# Schematics.net
KiCad netlist of a schematic drawn in Altium Designer
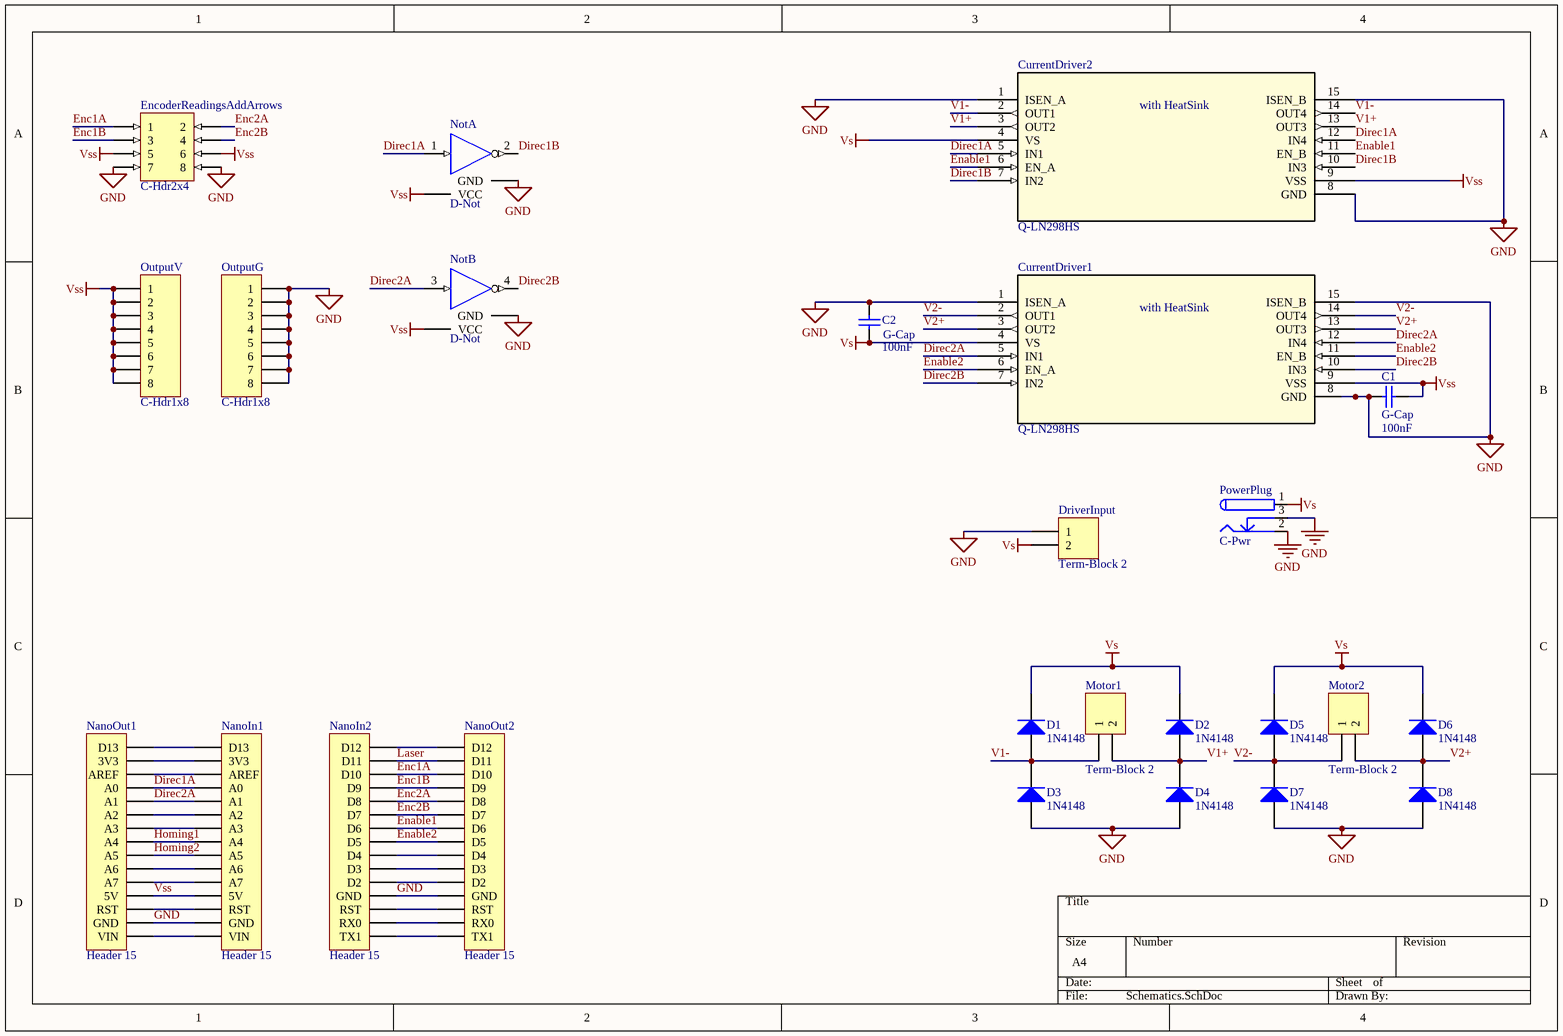
[diagram p0: Schematics.SchDoc]

(export (version "E")
  (design (tool "Eeschema 10.0.6"))
  (components
    (comp (ref "C1")
      (value "G-Cap")
      (footprint "Cap2.54mm_LGE1.0")
      (description "Capacitor (specify value)")
      (fields (field (name "ALTIUM_VALUE") "100nF") (field (name "PUBLISHER") "Altium Limited"))
      (libsource (lib "PartsDatabaseV16.1") (part "G-Cap"))
    )
    (comp (ref "C2")
      (value "G-Cap")
      (footprint "Cap2.54mm_LGE1.0")
      (description "Capacitor (specify value)")
      (fields (field (name "ALTIUM_VALUE") "100nF") (field (name "PUBLISHER") "Altium Limited"))
      (libsource (lib "PartsDatabaseV16.1") (part "G-Cap"))
    )
    (comp (ref "CurrentDriver1")
      (value "Q-LN298HS")
      (footprint "Multiwatt15_V_ELEC391HS")
      (description "LN298 - IC Bridge Driver Par 15Multiwatt")
      (fields
        (field (name "MANUFACTURER_PART_NUMBER") "L298N")
        (field (name "COPYRIGHT") "Copyright (C) 2015 Accelerated Designs. All rights reserved")
      )
      (libsource (lib "Additional Parts 391") (part "Q-LN298HS"))
    )
    (comp (ref "CurrentDriver2")
      (value "Q-LN298HS")
      (footprint "Multiwatt15_V_ELEC391HS")
      (description "LN298 - IC Bridge Driver Par 15Multiwatt")
      (fields
        (field (name "MANUFACTURER_PART_NUMBER") "L298N")
        (field (name "COPYRIGHT") "Copyright (C) 2015 Accelerated Designs. All rights reserved")
      )
      (libsource (lib "Additional Parts 391") (part "Q-LN298HS"))
    )
    (comp (ref "D1")
      (value "1N4148")
      (footprint "DO-41_XLGE1.2")
      (description "High-speed Diode")
      (libsource (lib "PartsDatabaseV16.1") (part "T-DiodeRect"))
    )
    (comp (ref "D2")
      (value "1N4148")
      (footprint "DO-41_XLGE1.2")
      (description "High-speed Diode")
      (libsource (lib "PartsDatabaseV16.1") (part "T-DiodeRect"))
    )
    (comp (ref "D3")
      (value "1N4148")
      (footprint "DO-41_XLGE1.2")
      (description "High-speed Diode")
      (libsource (lib "PartsDatabaseV16.1") (part "T-DiodeRect"))
    )
    (comp (ref "D4")
      (value "1N4148")
      (footprint "DO-41_XLGE1.2")
      (description "High-speed Diode")
      (libsource (lib "PartsDatabaseV16.1") (part "T-DiodeRect"))
    )
    (comp (ref "D5")
      (value "1N4148")
      (footprint "DO-41_XLGE1.2")
      (description "High-speed Diode")
      (libsource (lib "PartsDatabaseV16.1") (part "T-DiodeRect"))
    )
    (comp (ref "D6")
      (value "1N4148")
      (footprint "DO-41_XLGE1.2")
      (description "High-speed Diode")
      (libsource (lib "PartsDatabaseV16.1") (part "T-DiodeRect"))
    )
    (comp (ref "D7")
      (value "1N4148")
      (footprint "DO-41_XLGE1.2")
      (description "High-speed Diode")
      (libsource (lib "PartsDatabaseV16.1") (part "T-DiodeRect"))
    )
    (comp (ref "D8")
      (value "1N4148")
      (footprint "DO-41_XLGE1.2")
      (description "High-speed Diode")
      (libsource (lib "PartsDatabaseV16.1") (part "T-DiodeRect"))
    )
    (comp (ref "DriverInput")
      (value "Term-Block 2")
      (footprint "TERM-BLOCK-5.08MM-2POS")
      (description "Terminal-Block 1x2")
      (fields (field (name "PUBLISHER") "Altium Limited"))
      (libsource (lib "") (part "C-Block2_1"))
    )
    (comp (ref "EncoderReadingsAddArrows")
      (value "C-Hdr2x4")
      (footprint "HDR2X4_LGE1.0")
      (description "Header, 4-Pin, Dual row")
      (fields (field (name "PUBLISHER") "Altium Limited"))
      (libsource (lib "PartsDatabaseV16.1") (part "C-Hdr2x4"))
    )
    (comp (ref "Motor1")
      (value "Term-Block 2")
      (footprint "TERM-BLOCK-5.08MM-2POS")
      (description "Terminal-Block 1x2")
      (fields (field (name "PUBLISHER") "Altium Limited"))
      (libsource (lib "PartsDatabaseV16.1") (part "C-Block2"))
    )
    (comp (ref "Motor2")
      (value "Term-Block 2")
      (footprint "TERM-BLOCK-5.08MM-2POS")
      (description "Terminal-Block 1x2")
      (fields (field (name "PUBLISHER") "Altium Limited"))
      (libsource (lib "PartsDatabaseV16.1") (part "C-Block2"))
    )
    (comp (ref "NanoIn1")
      (value "Header 15")
      (footprint "HDR1X15")
      (description "Header, 15-Pin")
      (fields (field (name "PUBLISHER") "Altium Limited"))
      (libsource (lib "") (part "Header 15_1"))
    )
    (comp (ref "NanoIn2")
      (value "Header 15")
      (footprint "HDR1X15")
      (description "Header, 15-Pin")
      (fields (field (name "PUBLISHER") "Altium Limited"))
      (libsource (lib "Miscellaneous Connectors") (part "Header 15"))
    )
    (comp (ref "NanoOut1")
      (value "Header 15")
      (footprint "HDR1X15")
      (description "Header, 15-Pin")
      (fields (field (name "PUBLISHER") "Altium Limited"))
      (libsource (lib "Miscellaneous Connectors") (part "Header 15"))
    )
    (comp (ref "NanoOut2")
      (value "Header 15")
      (footprint "HDR1X15")
      (description "Header, 15-Pin")
      (fields (field (name "PUBLISHER") "Altium Limited"))
      (libsource (lib "") (part "Header 15_2"))
    )
    (comp (ref "Not")
      (value "D-Not")
      (footprint "DIP14_LGE1.0")
      (description "Hex NOT gate (inverter)")
      (fields (field (name "PUBLISHER") "Altium Limited"))
      (libsource (lib "PartsDatabaseV16.1") (part "D-Not"))
    )
    (comp (ref "OutputG")
      (value "C-Hdr1x8")
      (footprint "HDR1X8_LGE1.0")
      (description "Header, 8-Pin")
      (fields (field (name "PUBLISHER") "Altium Limited"))
      (libsource (lib "") (part "C-Hdr1x8_1"))
    )
    (comp (ref "OutputV")
      (value "C-Hdr1x8")
      (footprint "HDR1X8_LGE1.0")
      (description "Header, 8-Pin")
      (fields (field (name "PUBLISHER") "Altium Limited"))
      (libsource (lib "PartsDatabaseV16.1") (part "C-Hdr1x8"))
    )
    (comp (ref "PowerPlug")
      (value "C-Pwr")
      (footprint "KLD_XLGE1.2")
      (description "Low Voltage Power Supply Connector")
      (fields (field (name "PUBLISHER") "Altium Limited"))
      (libsource (lib "PartsDatabaseV16.1") (part "C-Pwr"))
    )
  )
  (nets
    (net (code "1") (name "/Direc1A") (class "Default")
      (node (ref "CurrentDriver2") (pin "12") (pinfunction "IN4_12") (pintype "input"))
      (node (ref "CurrentDriver2") (pin "5") (pinfunction "IN1_5") (pintype "input"))
      (node (ref "NanoIn1") (pin "4") (pinfunction "A0_4") (pintype "passive"))
      (node (ref "NanoOut1") (pin "4") (pinfunction "A0_4") (pintype "passive"))
      (node (ref "Not") (pin "1") (pinfunction "A_1") (pintype "input"))
    )
    (net (code "2") (name "/Direc1B") (class "Default")
      (node (ref "CurrentDriver2") (pin "10") (pinfunction "IN3_10") (pintype "input"))
      (node (ref "CurrentDriver2") (pin "7") (pinfunction "IN2_7") (pintype "input"))
      (node (ref "Not") (pin "2") (pinfunction "Y_2") (pintype "output"))
    )
    (net (code "3") (name "/Direc2A") (class "Default")
      (node (ref "CurrentDriver1") (pin "12") (pinfunction "IN4_12") (pintype "input"))
      (node (ref "CurrentDriver1") (pin "5") (pinfunction "IN1_5") (pintype "input"))
      (node (ref "NanoIn1") (pin "5") (pinfunction "A1_5") (pintype "passive"))
      (node (ref "NanoOut1") (pin "5") (pinfunction "A1_5") (pintype "passive"))
      (node (ref "Not") (pin "3") (pinfunction "A_3") (pintype "input"))
    )
    (net (code "4") (name "/Direc2B") (class "Default")
      (node (ref "CurrentDriver1") (pin "10") (pinfunction "IN3_10") (pintype "input"))
      (node (ref "CurrentDriver1") (pin "7") (pinfunction "IN2_7") (pintype "input"))
      (node (ref "Not") (pin "4") (pinfunction "Y_4") (pintype "output"))
    )
    (net (code "5") (name "/Enable1") (class "Default")
      (node (ref "CurrentDriver2") (pin "11") (pinfunction "EN_B_11") (pintype "input"))
      (node (ref "CurrentDriver2") (pin "6") (pinfunction "EN_A_6") (pintype "input"))
      (node (ref "NanoIn2") (pin "7") (pinfunction "A3_7") (pintype "passive"))
      (node (ref "NanoOut2") (pin "7") (pinfunction "D6_7") (pintype "passive"))
    )
    (net (code "6") (name "/Enable2") (class "Default")
      (node (ref "CurrentDriver1") (pin "11") (pinfunction "EN_B_11") (pintype "input"))
      (node (ref "CurrentDriver1") (pin "6") (pinfunction "EN_A_6") (pintype "input"))
      (node (ref "NanoIn2") (pin "8") (pinfunction "A4_8") (pintype "passive"))
      (node (ref "NanoOut2") (pin "8") (pinfunction "D5_8") (pintype "passive"))
    )
    (net (code "7") (name "/Enc1A") (class "Default")
      (node (ref "EncoderReadingsAddArrows") (pin "1") (pinfunction "1_1") (pintype "input"))
      (node (ref "NanoIn2") (pin "3") (pinfunction "AREF_3") (pintype "passive"))
      (node (ref "NanoOut2") (pin "3") (pinfunction "D10_3") (pintype "passive"))
    )
    (net (code "8") (name "/Enc1B") (class "Default")
      (node (ref "EncoderReadingsAddArrows") (pin "3") (pinfunction "3_3") (pintype "input"))
      (node (ref "NanoIn2") (pin "4") (pinfunction "A0_4") (pintype "passive"))
      (node (ref "NanoOut2") (pin "4") (pinfunction "D9_4") (pintype "passive"))
    )
    (net (code "9") (name "/Enc2A") (class "Default")
      (node (ref "EncoderReadingsAddArrows") (pin "2") (pinfunction "2_2") (pintype "input"))
      (node (ref "NanoIn2") (pin "5") (pinfunction "A1_5") (pintype "passive"))
      (node (ref "NanoOut2") (pin "5") (pinfunction "D8_5") (pintype "passive"))
    )
    (net (code "10") (name "/Enc2B") (class "Default")
      (node (ref "EncoderReadingsAddArrows") (pin "4") (pinfunction "4_4") (pintype "input"))
      (node (ref "NanoIn2") (pin "6") (pinfunction "A2_6") (pintype "passive"))
      (node (ref "NanoOut2") (pin "6") (pinfunction "D7_6") (pintype "passive"))
    )
    (net (code "11") (name "/Homing1") (class "Default")
      (node (ref "NanoIn1") (pin "8") (pinfunction "A4_8") (pintype "passive"))
      (node (ref "NanoOut1") (pin "8") (pinfunction "A4_8") (pintype "passive"))
    )
    (net (code "12") (name "/Homing2") (class "Default")
      (node (ref "NanoIn1") (pin "9") (pinfunction "A5_9") (pintype "passive"))
      (node (ref "NanoOut1") (pin "9") (pinfunction "A5_9") (pintype "passive"))
    )
    (net (code "13") (name "/Laser") (class "Default")
      (node (ref "NanoIn2") (pin "2") (pinfunction "3V3_2") (pintype "passive"))
      (node (ref "NanoOut2") (pin "2") (pinfunction "D11_2") (pintype "passive"))
    )
    (net (code "14") (name "/V1+") (class "Default")
      (node (ref "CurrentDriver2") (pin "13") (pinfunction "OUT3_13") (pintype "output"))
      (node (ref "CurrentDriver2") (pin "3") (pinfunction "OUT2_3") (pintype "output"))
      (node (ref "D2") (pin "1") (pinfunction "A_1") (pintype "passive"))
      (node (ref "D4") (pin "2") (pinfunction "K_2") (pintype "passive"))
      (node (ref "Motor1") (pin "2") (pinfunction "2_2") (pintype "passive"))
    )
    (net (code "15") (name "/V1-") (class "Default")
      (node (ref "CurrentDriver2") (pin "14") (pinfunction "OUT4_14") (pintype "output"))
      (node (ref "CurrentDriver2") (pin "2") (pinfunction "OUT1_2") (pintype "output"))
      (node (ref "D1") (pin "1") (pinfunction "A_1") (pintype "passive"))
      (node (ref "D3") (pin "2") (pinfunction "K_2") (pintype "passive"))
      (node (ref "Motor1") (pin "1") (pinfunction "1_1") (pintype "passive"))
    )
    (net (code "16") (name "/V2+") (class "Default")
      (node (ref "CurrentDriver1") (pin "13") (pinfunction "OUT3_13") (pintype "output"))
      (node (ref "CurrentDriver1") (pin "3") (pinfunction "OUT2_3") (pintype "output"))
      (node (ref "D6") (pin "1") (pinfunction "A_1") (pintype "passive"))
      (node (ref "D8") (pin "2") (pinfunction "K_2") (pintype "passive"))
      (node (ref "Motor2") (pin "2") (pinfunction "2_2") (pintype "passive"))
    )
    (net (code "17") (name "/V2-") (class "Default")
      (node (ref "CurrentDriver1") (pin "14") (pinfunction "OUT4_14") (pintype "output"))
      (node (ref "CurrentDriver1") (pin "2") (pinfunction "OUT1_2") (pintype "output"))
      (node (ref "D5") (pin "1") (pinfunction "A_1") (pintype "passive"))
      (node (ref "D7") (pin "2") (pinfunction "K_2") (pintype "passive"))
      (node (ref "Motor2") (pin "1") (pinfunction "1_1") (pintype "passive"))
    )
    (net (code "18") (name "GND") (class "Default")
      (node (ref "C1") (pin "1") (pinfunction "1_1") (pintype "passive"))
      (node (ref "C2") (pin "2") (pinfunction "2_2") (pintype "passive"))
      (node (ref "CurrentDriver1") (pin "1") (pinfunction "ISEN_A_1") (pintype "passive"))
      (node (ref "CurrentDriver1") (pin "15") (pinfunction "ISEN_B_15") (pintype "passive"))
      (node (ref "CurrentDriver1") (pin "8") (pinfunction "GND_8") (pintype "power_in"))
      (node (ref "CurrentDriver2") (pin "1") (pinfunction "ISEN_A_1") (pintype "passive"))
      (node (ref "CurrentDriver2") (pin "15") (pinfunction "ISEN_B_15") (pintype "passive"))
      (node (ref "CurrentDriver2") (pin "8") (pinfunction "GND_8") (pintype "power_in"))
      (node (ref "D3") (pin "1") (pinfunction "A_1") (pintype "passive"))
      (node (ref "D4") (pin "1") (pinfunction "A_1") (pintype "passive"))
      (node (ref "D7") (pin "1") (pinfunction "A_1") (pintype "passive"))
      (node (ref "D8") (pin "1") (pinfunction "A_1") (pintype "passive"))
      (node (ref "DriverInput") (pin "1") (pinfunction "1_1") (pintype "passive"))
      (node (ref "EncoderReadingsAddArrows") (pin "7") (pinfunction "7_7") (pintype "input"))
      (node (ref "EncoderReadingsAddArrows") (pin "8") (pinfunction "8_8") (pintype "input"))
      (node (ref "NanoIn1") (pin "14") (pinfunction "GND_14") (pintype "passive"))
      (node (ref "NanoIn2") (pin "12") (pinfunction "5V_12") (pintype "passive"))
      (node (ref "NanoOut1") (pin "14") (pinfunction "GND_14") (pintype "passive"))
      (node (ref "NanoOut2") (pin "12") (pinfunction "GND_12") (pintype "passive"))
      (node (ref "Not") (pin "7") (pinfunction "GND_7") (pintype "power_in"))
      (node (ref "OutputG") (pin "1") (pinfunction "1_1") (pintype "passive"))
      (node (ref "OutputG") (pin "2") (pinfunction "2_2") (pintype "passive"))
      (node (ref "OutputG") (pin "3") (pinfunction "3_3") (pintype "passive"))
      (node (ref "OutputG") (pin "4") (pinfunction "4_4") (pintype "passive"))
      (node (ref "OutputG") (pin "5") (pinfunction "5_5") (pintype "passive"))
      (node (ref "OutputG") (pin "6") (pinfunction "6_6") (pintype "passive"))
      (node (ref "OutputG") (pin "7") (pinfunction "7_7") (pintype "passive"))
      (node (ref "OutputG") (pin "8") (pinfunction "8_8") (pintype "passive"))
      (node (ref "PowerPlug") (pin "2") (pinfunction "2_2") (pintype "power_in"))
      (node (ref "PowerPlug") (pin "3") (pinfunction "3_3") (pintype "power_in"))
    )
    (net (code "19") (name "Net-(NanoIn1-3V3)") (class "Default")
      (node (ref "NanoIn1") (pin "2") (pinfunction "3V3_2") (pintype "passive"))
      (node (ref "NanoOut1") (pin "2") (pinfunction "3V3_2") (pintype "passive"))
    )
    (net (code "20") (name "Net-(NanoIn1-A2)") (class "Default")
      (node (ref "NanoIn1") (pin "6") (pinfunction "A2_6") (pintype "passive"))
      (node (ref "NanoOut1") (pin "6") (pinfunction "A2_6") (pintype "passive"))
    )
    (net (code "21") (name "Net-(NanoIn1-A3)") (class "Default")
      (node (ref "NanoIn1") (pin "7") (pinfunction "A3_7") (pintype "passive"))
      (node (ref "NanoOut1") (pin "7") (pinfunction "A3_7") (pintype "passive"))
    )
    (net (code "22") (name "Net-(NanoIn1-A6)") (class "Default")
      (node (ref "NanoIn1") (pin "10") (pinfunction "A6_10") (pintype "passive"))
      (node (ref "NanoOut1") (pin "10") (pinfunction "A6_10") (pintype "passive"))
    )
    (net (code "23") (name "Net-(NanoIn1-A7)") (class "Default")
      (node (ref "NanoIn1") (pin "11") (pinfunction "A7_11") (pintype "passive"))
      (node (ref "NanoOut1") (pin "11") (pinfunction "A7_11") (pintype "passive"))
    )
    (net (code "24") (name "Net-(NanoIn1-AREF)") (class "Default")
      (node (ref "NanoIn1") (pin "3") (pinfunction "AREF_3") (pintype "passive"))
      (node (ref "NanoOut1") (pin "3") (pinfunction "AREF_3") (pintype "passive"))
    )
    (net (code "25") (name "Net-(NanoIn1-D13)") (class "Default")
      (node (ref "NanoIn1") (pin "1") (pinfunction "D13_1") (pintype "passive"))
      (node (ref "NanoOut1") (pin "1") (pinfunction "D13_1") (pintype "passive"))
    )
    (net (code "26") (name "Net-(NanoIn1-RST)") (class "Default")
      (node (ref "NanoIn1") (pin "13") (pinfunction "RST_13") (pintype "passive"))
      (node (ref "NanoOut1") (pin "13") (pinfunction "RST_13") (pintype "passive"))
    )
    (net (code "27") (name "Net-(NanoIn1-VIN)") (class "Default")
      (node (ref "NanoIn1") (pin "15") (pinfunction "VIN_15") (pintype "passive"))
      (node (ref "NanoOut1") (pin "15") (pinfunction "VIN_15") (pintype "passive"))
    )
    (net (code "28") (name "Net-(NanoIn2-A5)") (class "Default")
      (node (ref "NanoIn2") (pin "9") (pinfunction "A5_9") (pintype "passive"))
      (node (ref "NanoOut2") (pin "9") (pinfunction "D4_9") (pintype "passive"))
    )
    (net (code "29") (name "Net-(NanoIn2-A6)") (class "Default")
      (node (ref "NanoIn2") (pin "10") (pinfunction "A6_10") (pintype "passive"))
      (node (ref "NanoOut2") (pin "10") (pinfunction "D3_10") (pintype "passive"))
    )
    (net (code "30") (name "Net-(NanoIn2-A7)") (class "Default")
      (node (ref "NanoIn2") (pin "11") (pinfunction "A7_11") (pintype "passive"))
      (node (ref "NanoOut2") (pin "11") (pinfunction "D2_11") (pintype "passive"))
    )
    (net (code "31") (name "Net-(NanoIn2-D13)") (class "Default")
      (node (ref "NanoIn2") (pin "1") (pinfunction "D13_1") (pintype "passive"))
      (node (ref "NanoOut2") (pin "1") (pinfunction "D12_1") (pintype "passive"))
    )
    (net (code "32") (name "Net-(NanoIn2-GND)") (class "Default")
      (node (ref "NanoIn2") (pin "14") (pinfunction "GND_14") (pintype "passive"))
      (node (ref "NanoOut2") (pin "14") (pinfunction "RX0_14") (pintype "passive"))
    )
    (net (code "33") (name "Net-(NanoIn2-RST)") (class "Default")
      (node (ref "NanoIn2") (pin "13") (pinfunction "RST_13") (pintype "passive"))
      (node (ref "NanoOut2") (pin "13") (pinfunction "RST_13") (pintype "passive"))
    )
    (net (code "34") (name "Net-(NanoIn2-VIN)") (class "Default")
      (node (ref "NanoIn2") (pin "15") (pinfunction "VIN_15") (pintype "passive"))
      (node (ref "NanoOut2") (pin "15") (pinfunction "TX1_15") (pintype "passive"))
    )
    (net (code "35") (name "Vs") (class "Default")
      (node (ref "C2") (pin "1") (pinfunction "1_1") (pintype "passive"))
      (node (ref "CurrentDriver1") (pin "4") (pinfunction "VS_4") (pintype "power_in"))
      (node (ref "CurrentDriver2") (pin "4") (pinfunction "VS_4") (pintype "power_in"))
      (node (ref "D1") (pin "2") (pinfunction "K_2") (pintype "passive"))
      (node (ref "D2") (pin "2") (pinfunction "K_2") (pintype "passive"))
      (node (ref "D5") (pin "2") (pinfunction "K_2") (pintype "passive"))
      (node (ref "D6") (pin "2") (pinfunction "K_2") (pintype "passive"))
      (node (ref "DriverInput") (pin "2") (pinfunction "2_2") (pintype "passive"))
      (node (ref "PowerPlug") (pin "1") (pinfunction "1_1") (pintype "power_in"))
    )
    (net (code "36") (name "Vss") (class "Default")
      (node (ref "C1") (pin "2") (pinfunction "2_2") (pintype "passive"))
      (node (ref "CurrentDriver1") (pin "9") (pinfunction "VSS_9") (pintype "power_in"))
      (node (ref "CurrentDriver2") (pin "9") (pinfunction "VSS_9") (pintype "power_in"))
      (node (ref "EncoderReadingsAddArrows") (pin "5") (pinfunction "5_5") (pintype "input"))
      (node (ref "EncoderReadingsAddArrows") (pin "6") (pinfunction "6_6") (pintype "input"))
      (node (ref "NanoIn1") (pin "12") (pinfunction "5V_12") (pintype "passive"))
      (node (ref "NanoOut1") (pin "12") (pinfunction "5V_12") (pintype "passive"))
      (node (ref "Not") (pin "14") (pinfunction "VCC_14") (pintype "power_in"))
      (node (ref "OutputV") (pin "1") (pinfunction "1_1") (pintype "passive"))
      (node (ref "OutputV") (pin "2") (pinfunction "2_2") (pintype "passive"))
      (node (ref "OutputV") (pin "3") (pinfunction "3_3") (pintype "passive"))
      (node (ref "OutputV") (pin "4") (pinfunction "4_4") (pintype "passive"))
      (node (ref "OutputV") (pin "5") (pinfunction "5_5") (pintype "passive"))
      (node (ref "OutputV") (pin "6") (pinfunction "6_6") (pintype "passive"))
      (node (ref "OutputV") (pin "7") (pinfunction "7_7") (pintype "passive"))
      (node (ref "OutputV") (pin "8") (pinfunction "8_8") (pintype "passive"))
    )
  )
)
